# ShinStrap_Interface.net
KiCad netlist of a schematic drawn in Altium Designer
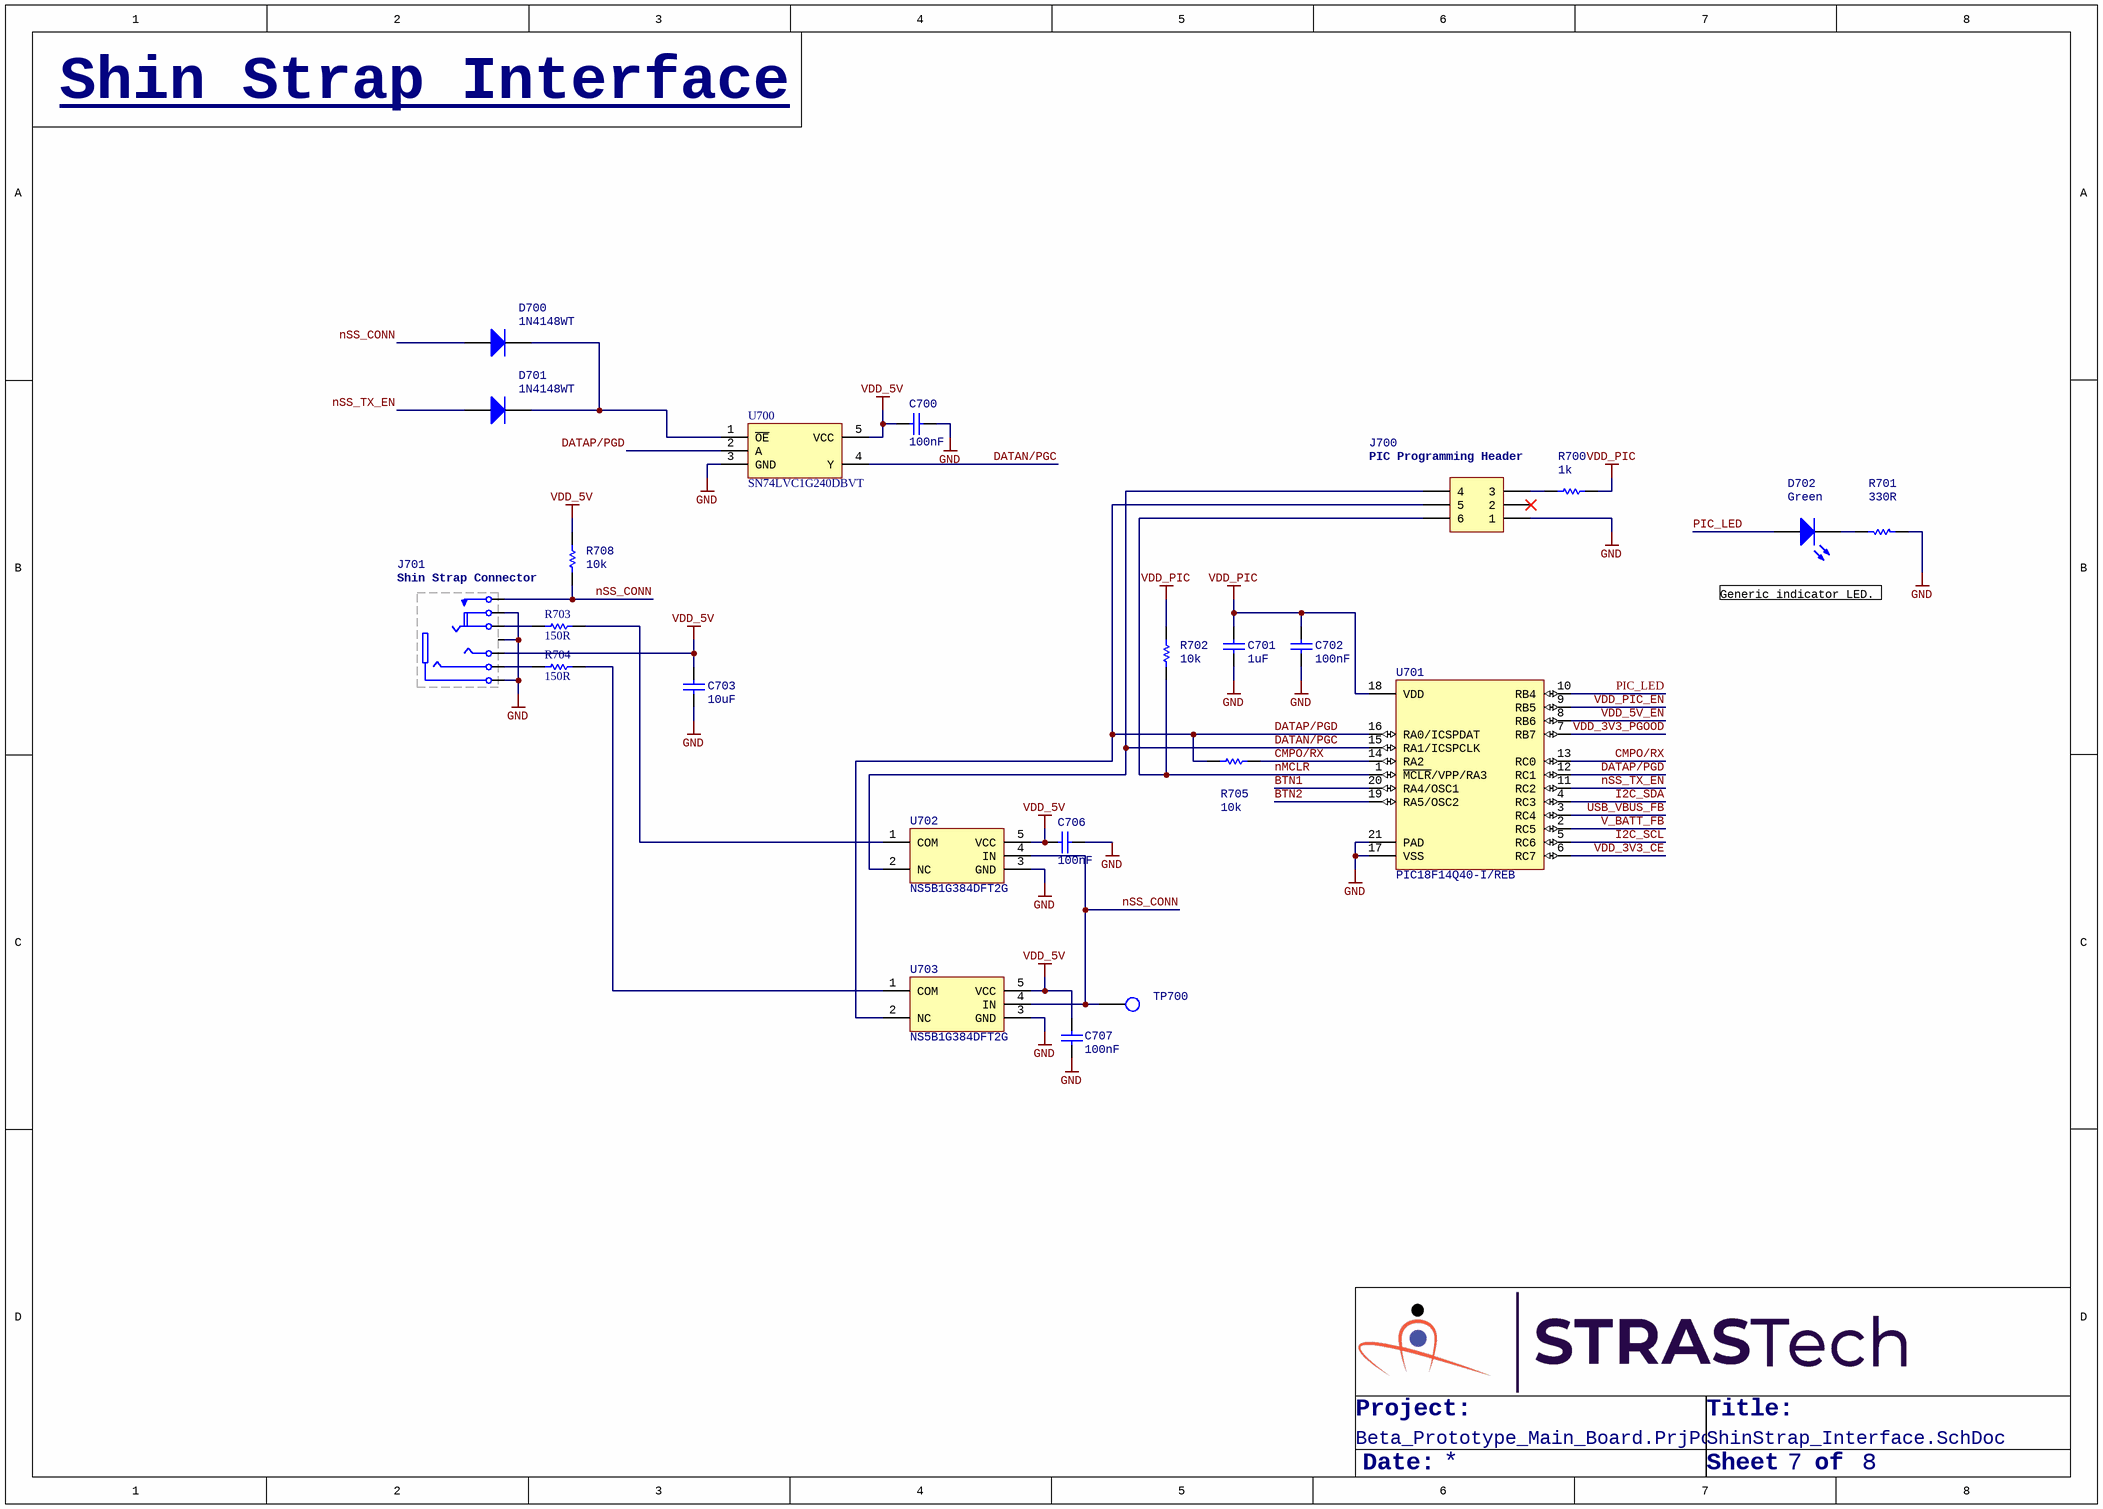
[diagram p0: ShinStrap_Interface.SchDoc]

(export (version "E")
  (design (tool "Eeschema 10.0.6"))
  (components
    (comp (ref "C700")
      (value "100nF")
      (footprint "Cap,SMD,0402")
      (description "0.1µF ±10% 25V Ceramic Capacitor X7R 0402 (1005 Metric)")
      (fields
        (field (name "VENDOR PART NUMBER") "490-14603-1-ND")
        (field (name "MANUFACTURER") "Murata Electronics")
        (field (name "CREATEDBY") "Judd Foster")
      )
      (libsource (lib "symbols") (part "CAP,Cer,100nF,25VDC,X7R,0402"))
    )
    (comp (ref "C701")
      (value "1uF")
      (footprint "Cap,SMD,0402")
      (description "1 µF ±10% 35V Ceramic Capacitor X5R 0402 (1005 Metric)")
      (fields
        (field (name "VENDOR PART NUMBER") "445-9073-1-ND")
        (field (name "MANUFACTURER") "TDK Corporation")
        (field (name "CREATEDBY") "Judd Foster")
      )
      (libsource (lib "symbols") (part "CAP,Cer,1uF,35VDC,X5R,0402"))
    )
    (comp (ref "C702")
      (value "100nF")
      (footprint "Cap,SMD,0402")
      (description "0.1µF ±10% 25V Ceramic Capacitor X7R 0402 (1005 Metric)")
      (fields
        (field (name "VENDOR PART NUMBER") "490-14603-1-ND")
        (field (name "MANUFACTURER") "Murata Electronics")
        (field (name "CREATEDBY") "Judd Foster")
      )
      (libsource (lib "symbols") (part "CAP,Cer,100nF,25VDC,X7R,0402"))
    )
    (comp (ref "C703")
      (value "10uF")
      (footprint "Cap,SMD,0402")
      (description "10 µF ±20% 10V Ceramic Capacitor X5R 0402 (1005 Metric)")
      (fields
        (field (name "VENDOR PART NUMBER") "1276-1450-1-ND")
        (field (name "MANUFACTURER") "Samsung Electro-Mechanics")
        (field (name "CREATEDBY") "Judd Foster")
      )
      (libsource (lib "symbols") (part "CAP,Cer,10uF,10VDC,X5R,0402"))
    )
    (comp (ref "C706")
      (value "100nF")
      (footprint "Cap,SMD,0402")
      (description "0.1µF ±10% 25V Ceramic Capacitor X7R 0402 (1005 Metric)")
      (fields
        (field (name "VENDOR PART NUMBER") "490-14603-1-ND")
        (field (name "MANUFACTURER") "Murata Electronics")
        (field (name "CREATEDBY") "Judd Foster")
      )
      (libsource (lib "symbols") (part "CAP,Cer,100nF,25VDC,X7R,0402"))
    )
    (comp (ref "C707")
      (value "100nF")
      (footprint "Cap,SMD,0402")
      (description "0.1µF ±10% 25V Ceramic Capacitor X7R 0402 (1005 Metric)")
      (fields
        (field (name "VENDOR PART NUMBER") "490-14603-1-ND")
        (field (name "MANUFACTURER") "Murata Electronics")
        (field (name "CREATEDBY") "Judd Foster")
      )
      (libsource (lib "symbols") (part "CAP,Cer,100nF,25VDC,X7R,0402"))
    )
    (comp (ref "D700")
      (value "1N4148WT")
      (footprint "SOD523")
      (description "Diode Standard 75 V 200mA Surface Mount SOD-523F")
      (fields
        (field (name "MANUFACTURER") "ON Semiconductor")
        (field (name "VENDOR PART NUMBER") "1N4148WTCT-ND")
        (field (name "CREATEDBY") "Judd Foster")
      )
      (libsource (lib "symbols") (part "DIODE,Gen,75V,200mA,SOD523F"))
    )
    (comp (ref "D701")
      (value "1N4148WT")
      (footprint "SOD523")
      (description "Diode Standard 75 V 200mA Surface Mount SOD-523F")
      (fields
        (field (name "MANUFACTURER") "ON Semiconductor")
        (field (name "VENDOR PART NUMBER") "1N4148WTCT-ND")
        (field (name "CREATEDBY") "Judd Foster")
      )
      (libsource (lib "symbols") (part "DIODE,Gen,75V,200mA,SOD523F"))
    )
    (comp (ref "D702")
      (value "Green")
      (footprint "LED,0603")
      (description "Green 530nm LED Indication - Discrete 3V 0603 (1608 Metric)")
      (fields
        (field (name "MANUFACTURER") "Stanley Electric Co")
        (field (name "MANUFACTURER PART NUMBER") "THG1111C-0005-TR")
        (field (name "CREATEDBY") "Judd Foster")
      )
      (libsource (lib "symbols") (part "LED,Green,SMD,0603"))
    )
    (comp (ref "J700")
      (value "Term,Header,3x2 Pin,1.27mm,SMD")
      (footprint "TERM,HEADER,3X2PIN,P1.27,SMD")
      (description "Connector Header Surface Mount 6 position 0.050\" (1.27mm)")
      (fields
        (field (name "VENDOR PART NUMBER") "609-3693-1-ND")
        (field (name "MANUFACTURER") "Amphenol ICC (FCI)")
        (field (name "CREATEDBY") "Judd Foster")
      )
      (libsource (lib "symbols") (part "Term,Header,3x2 Pin,1.27mm,SMD"))
    )
    (comp (ref "J701")
      (value "Conn,Jack,TRS,3.5mm,Thru,Shielded")
      (footprint "Conn,Jack,TRS,3.5mm,Thru,Shielded")
      (fields
        (field (name "MANUFACTURER") "CUI Devices")
        (field (name "MANUFACTURER PART NUMBER") "SJ-435107RS")
        (field (name "VENDOR PART NUMBER") "CP-435107RS-ND")
        (field (name "CREATEDBY") "Judd Foster")
      )
      (libsource (lib "symbols") (part "Conn,Jack,TRS,3.5mm,Thru,Shielded"))
    )
    (comp (ref "R700")
      (value "1k")
      (footprint "RES,0402")
      (description "1 kOhms ±5% 0.063W, 1/16W Chip Resistor 0402 (1005 Metric) Automotive AEC-Q200 Thick Film")
      (fields
        (field (name "VENDOR PART NUMBER") "RMCF0402JT1K00CT-ND")
        (field (name "MANUFACTURER") "Stackpole Electronics Inc")
        (field (name "CREATEDBY") "Judd Foster")
      )
      (libsource (lib "symbols") (part "RES,1k,5%,0.063W,0402"))
    )
    (comp (ref "R701")
      (value "330R")
      (footprint "RES,0402")
      (description "330 Ohms ±5% 0.063W, 1/16W Chip Resistor 0402 (1005 Metric) Automotive AEC-Q200 Thick Film")
      (fields
        (field (name "MANUFACTURER") "Stackpole Electronics Inc")
        (field (name "MANUFACTURER PART NUMBER") "RMCF0402JT330R")
        (field (name "CREATEDBY") "Judd Foster")
      )
      (libsource (lib "symbols") (part "RES,330R,5%,0.063W,0402"))
    )
    (comp (ref "R702")
      (value "10k")
      (footprint "RES,0402")
      (description "10 kOhms ±5% 0.063W, 1/16W Chip Resistor 0402 (1005 Metric) Automotive AEC-Q200 Thick Film")
      (fields
        (field (name "VENDOR PART NUMBER") "RMCF0402JT10K0CT-ND")
        (field (name "MANUFACTURER") "Stackpole Electronics Inc")
        (field (name "CREATEDBY") "Judd Foster")
      )
      (libsource (lib "symbols") (part "RES,10k,5%,0.063W,0402"))
    )
    (comp (ref "R703")
      (value "150R")
      (footprint "RES,0402")
      (fields
        (field (name "MANUFACTURER") "TE Connectivity Passive Product")
        (field (name "MANUFACTURER PART NUMBER") "CRGCQ0402F150R")
        (field (name "VENDOR PART NUMBER") "A129617CT-ND")
        (field (name "CREATEDBY") "Judd Foster")
      )
      (libsource (lib "symbols") (part "RES,150R,1%,0.1W,0402"))
    )
    (comp (ref "R704")
      (value "150R")
      (footprint "RES,0402")
      (fields
        (field (name "MANUFACTURER") "TE Connectivity Passive Product")
        (field (name "MANUFACTURER PART NUMBER") "CRGCQ0402F150R")
        (field (name "VENDOR PART NUMBER") "A129617CT-ND")
        (field (name "CREATEDBY") "Judd Foster")
      )
      (libsource (lib "symbols") (part "RES,150R,1%,0.1W,0402"))
    )
    (comp (ref "R705")
      (value "10k")
      (footprint "RES,0402")
      (description "10 kOhms ±5% 0.063W, 1/16W Chip Resistor 0402 (1005 Metric) Automotive AEC-Q200 Thick Film")
      (fields
        (field (name "VENDOR PART NUMBER") "RMCF0402JT10K0CT-ND")
        (field (name "MANUFACTURER") "Stackpole Electronics Inc")
        (field (name "CREATEDBY") "Judd Foster")
      )
      (libsource (lib "symbols") (part "RES,10k,5%,0.063W,0402"))
    )
    (comp (ref "R708")
      (value "10k")
      (footprint "RES,0402")
      (description "10 kOhms ±5% 0.063W, 1/16W Chip Resistor 0402 (1005 Metric) Automotive AEC-Q200 Thick Film")
      (fields
        (field (name "VENDOR PART NUMBER") "RMCF0402JT10K0CT-ND")
        (field (name "MANUFACTURER") "Stackpole Electronics Inc")
        (field (name "CREATEDBY") "Judd Foster")
      )
      (libsource (lib "symbols") (part "RES,10k,5%,0.063W,0402"))
    )
    (comp (ref "TP700")
      (value "TESTPOINT")
      (footprint "testpoint,smd,round,1mm")
      (description "PCB Testpoint")
      (fields (field (name "CREATEDBY") "Judd Foster"))
      (libsource (lib "symbols") (part "TESTPOINT"))
    )
    (comp (ref "U700")
      (value "SN74LVC1G240DBVT")
      (footprint "sot23-5")
      (description "Buffer, Inverting 1 Element 1 Bit per Element 3-State Output SOT-23-5")
      (fields
        (field (name "VENDOR PART NUMBER") "296-32301-1-ND")
        (field (name "MANUFACTURER") "Texas Instruments")
        (field (name "CREATEDBY") "Judd Foster")
      )
      (libsource (lib "symbols") (part "SN74LVC1G240DBVT"))
    )
    (comp (ref "U701")
      (value "PIC18F14Q40-I/REB")
      (footprint "IC,QFN-20,3x3,PAD,P0.4")
      (description "PIC series Microcontroller IC 8-Bit 64MHz 16KB (16K x 8) FLASH 20-VQFN (3x3)")
      (fields
        (field (name "MANUFACTURER") "Microchip Technology")
        (field (name "VENDOR PART NUMBER") "150-PIC18F14Q40-I/REB-ND")
        (field (name "CREATEDBY") "Judd Foster")
      )
      (libsource (lib "symbols") (part "PIC18F14Q40-I/REB"))
    )
    (comp (ref "U702")
      (value "NS5B1G384DFT2G")
      (footprint "SC70-5")
      (description "1 Circuit IC Switch 1:1 15Ohm SC-88A (SC-70-5/SOT-353)")
      (fields
        (field (name "MANUFACTURER") "onsemi")
        (field (name "VENDOR PART NUMBER") "NS5B1G384DFT2GOSCT-ND")
        (field (name "CREATEDBY") "Judd Foster")
      )
      (libsource (lib "symbols") (part "NS5B1G384DFT2G"))
    )
    (comp (ref "U703")
      (value "NS5B1G384DFT2G")
      (footprint "SC70-5")
      (description "1 Circuit IC Switch 1:1 15Ohm SC-88A (SC-70-5/SOT-353)")
      (fields
        (field (name "MANUFACTURER") "onsemi")
        (field (name "VENDOR PART NUMBER") "NS5B1G384DFT2GOSCT-ND")
        (field (name "CREATEDBY") "Judd Foster")
      )
      (libsource (lib "symbols") (part "NS5B1G384DFT2G"))
    )
  )
  (nets
    (net (code "1") (name "/BTN1") (class "Default")
      (node (ref "U701") (pin "20") (pinfunction "RA4/OSC1_20") (pintype "bidirectional"))
    )
    (net (code "2") (name "/BTN2") (class "Default")
      (node (ref "U701") (pin "19") (pinfunction "RA5/OSC2_19") (pintype "bidirectional"))
    )
    (net (code "3") (name "/CMPO{slash}RX") (class "Default")
      (node (ref "R705") (pin "1") (pinfunction "1_1") (pintype "passive"))
      (node (ref "U701") (pin "13") (pinfunction "RC0_13") (pintype "bidirectional"))
      (node (ref "U701") (pin "14") (pinfunction "RA2_14") (pintype "bidirectional"))
    )
    (net (code "4") (name "/DATAN{slash}PGC") (class "Default")
      (node (ref "J700") (pin "4") (pinfunction "4_4") (pintype "passive"))
      (node (ref "U700") (pin "4") (pinfunction "Y_4") (pintype "passive"))
      (node (ref "U701") (pin "15") (pinfunction "RA1/ICSPCLK_15") (pintype "bidirectional"))
      (node (ref "U702") (pin "2") (pinfunction "NC_2") (pintype "passive"))
    )
    (net (code "5") (name "/DATAP{slash}PGD") (class "Default")
      (node (ref "J700") (pin "5") (pinfunction "5_5") (pintype "passive"))
      (node (ref "R705") (pin "2") (pinfunction "2_2") (pintype "passive"))
      (node (ref "U700") (pin "2") (pinfunction "A_2") (pintype "passive"))
      (node (ref "U701") (pin "12") (pinfunction "RC1_12") (pintype "bidirectional"))
      (node (ref "U701") (pin "16") (pinfunction "RA0/ICSPDAT_16") (pintype "bidirectional"))
      (node (ref "U703") (pin "2") (pinfunction "NC_2") (pintype "passive"))
    )
    (net (code "6") (name "/I2C_SCL") (class "Default")
      (node (ref "U701") (pin "5") (pinfunction "RC6_5") (pintype "bidirectional"))
    )
    (net (code "7") (name "/I2C_SDA") (class "Default")
      (node (ref "U701") (pin "4") (pinfunction "RC3_4") (pintype "bidirectional"))
    )
    (net (code "8") (name "/PIC_LED") (class "Default")
      (node (ref "D702") (pin "1") (pinfunction "A_1") (pintype "passive"))
      (node (ref "U701") (pin "10") (pinfunction "RB4_10") (pintype "bidirectional"))
    )
    (net (code "9") (name "/USB_VBUS_FB") (class "Default")
      (node (ref "U701") (pin "3") (pinfunction "RC4_3") (pintype "bidirectional"))
    )
    (net (code "10") (name "/VDD_3V3_CE") (class "Default")
      (node (ref "U701") (pin "6") (pinfunction "RC7_6") (pintype "bidirectional"))
    )
    (net (code "11") (name "/VDD_3V3_PGOOD") (class "Default")
      (node (ref "U701") (pin "7") (pinfunction "RB7_7") (pintype "bidirectional"))
    )
    (net (code "12") (name "/VDD_5V_EN") (class "Default")
      (node (ref "U701") (pin "8") (pinfunction "RB6_8") (pintype "bidirectional"))
    )
    (net (code "13") (name "/VDD_PIC_EN") (class "Default")
      (node (ref "U701") (pin "9") (pinfunction "RB5_9") (pintype "bidirectional"))
    )
    (net (code "14") (name "/V_BATT_FB") (class "Default")
      (node (ref "U701") (pin "2") (pinfunction "RC5_2") (pintype "bidirectional"))
    )
    (net (code "15") (name "/nMCLR") (class "Default")
      (node (ref "J700") (pin "6") (pinfunction "6_6") (pintype "passive"))
      (node (ref "R702") (pin "1") (pinfunction "1_1") (pintype "passive"))
      (node (ref "U701") (pin "1") (pinfunction "~{MCLR}/VPP/RA3_1") (pintype "bidirectional"))
    )
    (net (code "16") (name "/nSS_CONN") (class "Default")
      (node (ref "D700") (pin "2") (pinfunction "A_2") (pintype "passive"))
      (node (ref "J701") (pin "6") (pinfunction "R1S_6") (pintype "passive"))
      (node (ref "R708") (pin "1") (pinfunction "1_1") (pintype "passive"))
      (node (ref "TP700") (pin "1") (pinfunction "TP_1") (pintype "passive"))
      (node (ref "U702") (pin "4") (pinfunction "IN_4") (pintype "passive"))
      (node (ref "U703") (pin "4") (pinfunction "IN_4") (pintype "passive"))
    )
    (net (code "17") (name "/nSS_TX_EN") (class "Default")
      (node (ref "D701") (pin "2") (pinfunction "A_2") (pintype "passive"))
      (node (ref "U701") (pin "11") (pinfunction "RC2_11") (pintype "bidirectional"))
    )
    (net (code "18") (name "GND") (class "Default")
      (node (ref "C700") (pin "1") (pinfunction "1_1") (pintype "passive"))
      (node (ref "C701") (pin "1") (pinfunction "1_1") (pintype "passive"))
      (node (ref "C702") (pin "1") (pinfunction "1_1") (pintype "passive"))
      (node (ref "C703") (pin "1") (pinfunction "1_1") (pintype "passive"))
      (node (ref "C706") (pin "2") (pinfunction "2_2") (pintype "passive"))
      (node (ref "C707") (pin "1") (pinfunction "1_1") (pintype "passive"))
      (node (ref "J700") (pin "1") (pinfunction "1_1") (pintype "passive"))
      (node (ref "J701") (pin "0") (pinfunction "SH_0") (pintype "power_in"))
      (node (ref "J701") (pin "1") (pinfunction "S_1") (pintype "power_in"))
      (node (ref "J701") (pin "5") (pinfunction "IR1_5") (pintype "passive"))
      (node (ref "R701") (pin "1") (pinfunction "1_1") (pintype "passive"))
      (node (ref "U700") (pin "3") (pinfunction "GND_3") (pintype "passive"))
      (node (ref "U701") (pin "17") (pinfunction "VSS_17") (pintype "power_in"))
      (node (ref "U701") (pin "21") (pinfunction "PAD_21") (pintype "passive"))
      (node (ref "U702") (pin "3") (pinfunction "GND_3") (pintype "passive"))
      (node (ref "U703") (pin "3") (pinfunction "GND_3") (pintype "passive"))
    )
    (net (code "19") (name "Net-(D700-K)") (class "Default")
      (node (ref "D700") (pin "1") (pinfunction "K_1") (pintype "passive"))
      (node (ref "D701") (pin "1") (pinfunction "K_1") (pintype "passive"))
      (node (ref "U700") (pin "1") (pinfunction "~{OE}_1") (pintype "passive"))
    )
    (net (code "20") (name "Net-(D702-K)") (class "Default")
      (node (ref "D702") (pin "2") (pinfunction "K_2") (pintype "passive"))
      (node (ref "R701") (pin "2") (pinfunction "2_2") (pintype "passive"))
    )
    (net (code "21") (name "Net-(J700-Pad3)") (class "Default")
      (node (ref "J700") (pin "3") (pinfunction "3_3") (pintype "passive"))
      (node (ref "R700") (pin "1") (pinfunction "1_1") (pintype "passive"))
    )
    (net (code "22") (name "Net-(J701-R1)") (class "Default")
      (node (ref "J701") (pin "3") (pinfunction "R1_3") (pintype "passive"))
      (node (ref "R703") (pin "1") (pinfunction "1_1") (pintype "passive"))
    )
    (net (code "23") (name "Net-(J701-R2)") (class "Default")
      (node (ref "J701") (pin "4") (pinfunction "R2_4") (pintype "passive"))
      (node (ref "R704") (pin "1") (pinfunction "1_1") (pintype "passive"))
    )
    (net (code "24") (name "Net-(U702-COM)") (class "Default")
      (node (ref "R703") (pin "2") (pinfunction "2_2") (pintype "passive"))
      (node (ref "U702") (pin "1") (pinfunction "COM_1") (pintype "passive"))
    )
    (net (code "25") (name "Net-(U703-COM)") (class "Default")
      (node (ref "R704") (pin "2") (pinfunction "2_2") (pintype "passive"))
      (node (ref "U703") (pin "1") (pinfunction "COM_1") (pintype "passive"))
    )
    (net (code "26") (name "VDD_5V") (class "Default")
      (node (ref "C700") (pin "2") (pinfunction "2_2") (pintype "passive"))
      (node (ref "C703") (pin "2") (pinfunction "2_2") (pintype "passive"))
      (node (ref "C706") (pin "1") (pinfunction "1_1") (pintype "passive"))
      (node (ref "C707") (pin "2") (pinfunction "2_2") (pintype "passive"))
      (node (ref "J701") (pin "2") (pinfunction "T_2") (pintype "passive"))
      (node (ref "R708") (pin "2") (pinfunction "2_2") (pintype "passive"))
      (node (ref "U700") (pin "5") (pinfunction "VCC_5") (pintype "passive"))
      (node (ref "U702") (pin "5") (pinfunction "VCC_5") (pintype "passive"))
      (node (ref "U703") (pin "5") (pinfunction "VCC_5") (pintype "passive"))
    )
    (net (code "27") (name "VDD_PIC") (class "Default")
      (node (ref "C701") (pin "2") (pinfunction "2_2") (pintype "passive"))
      (node (ref "C702") (pin "2") (pinfunction "2_2") (pintype "passive"))
      (node (ref "R700") (pin "2") (pinfunction "2_2") (pintype "passive"))
      (node (ref "R702") (pin "2") (pinfunction "2_2") (pintype "passive"))
      (node (ref "U701") (pin "18") (pinfunction "VDD_18") (pintype "power_in"))
    )
    (net (code "28") (name "unconnected-(J700-Pad2)") (class "Default")
      (node (ref "J700") (pin "2") (pinfunction "2_2") (pintype "passive+no_connect"))
    )
  )
)
